# Reaccion-Minimo.net
KiCad netlist of a schematic drawn in EAGLE
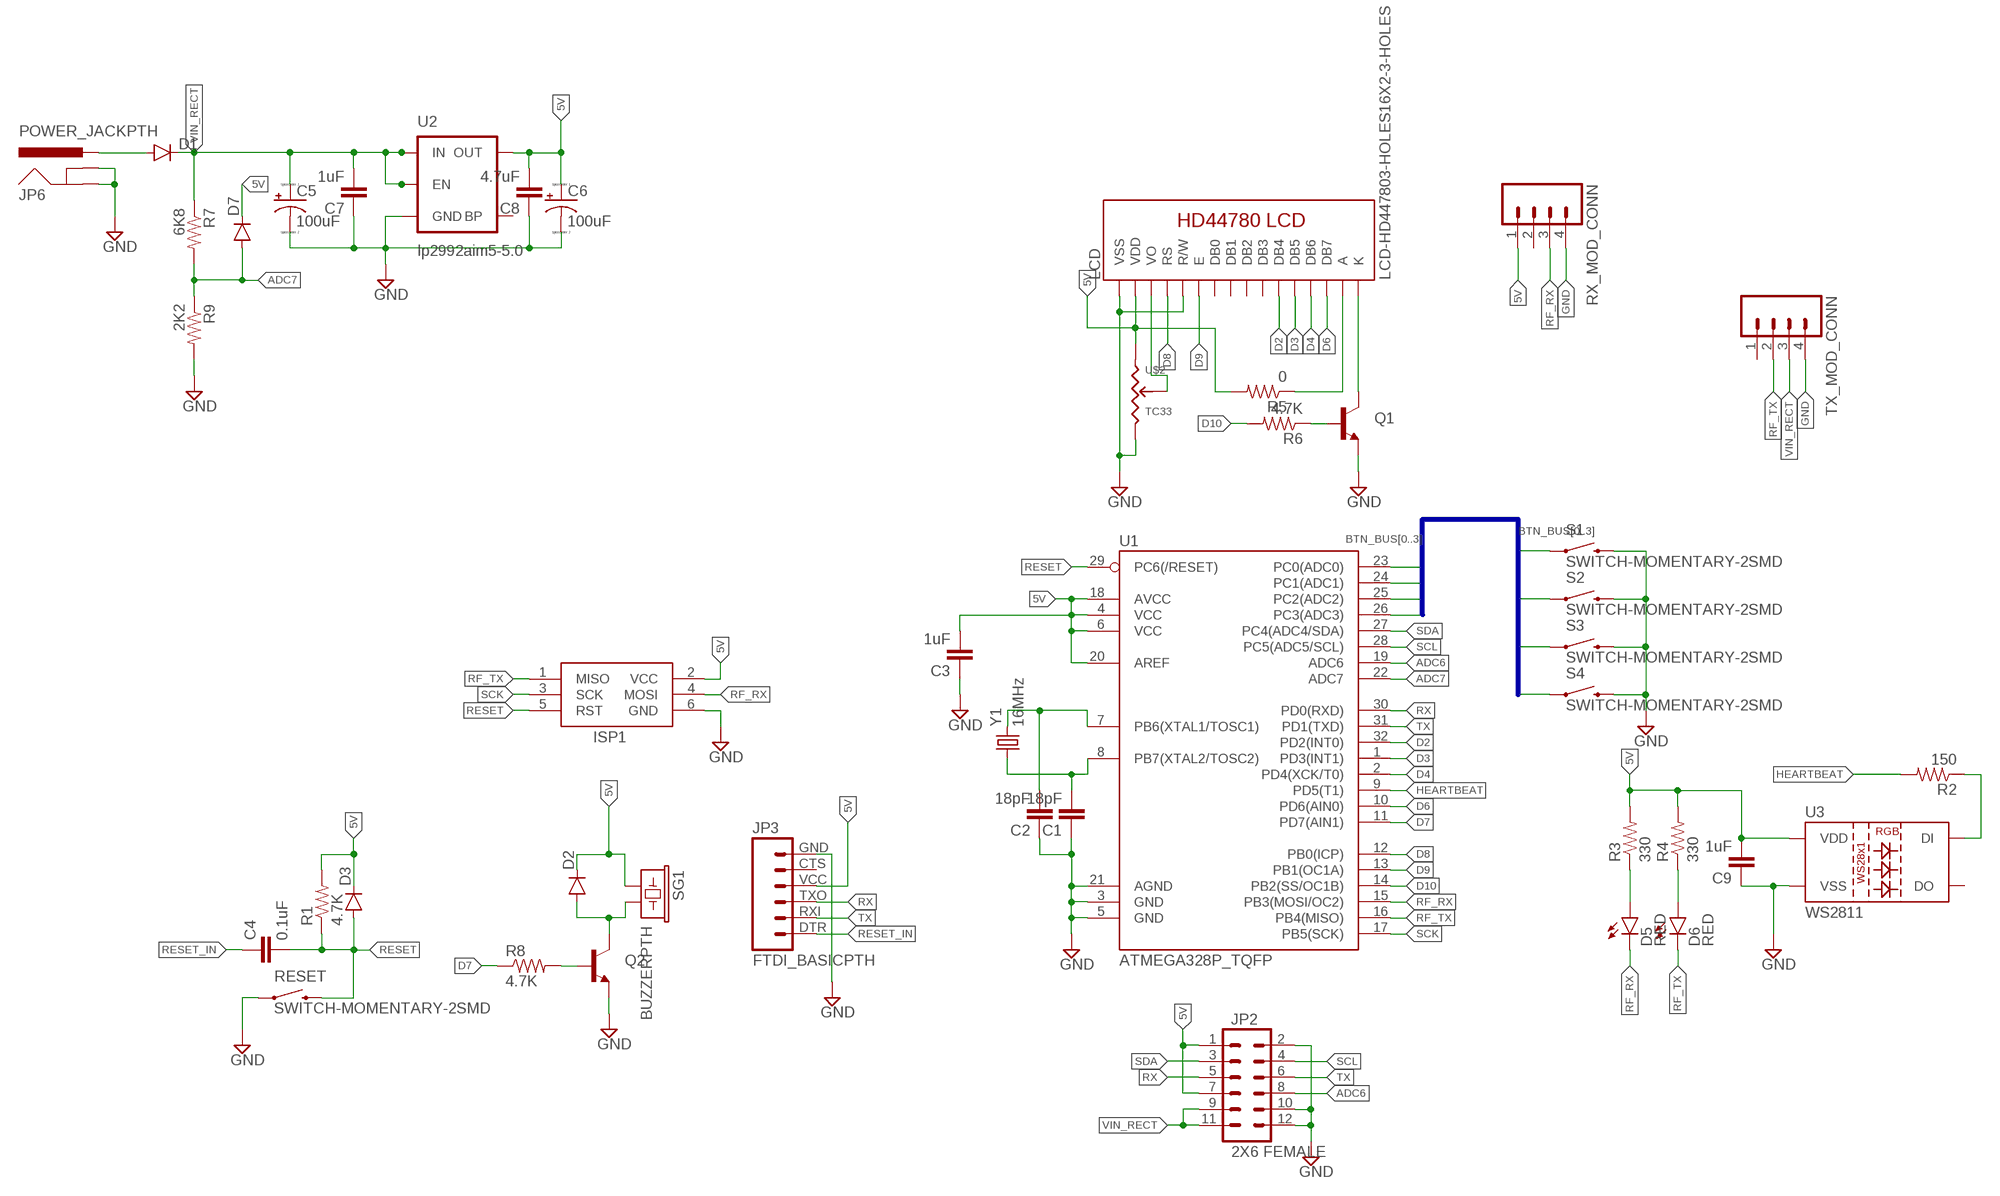
[diagram p0: schematic, sheet 1]

(export (version "E")
  (design (tool "Eeschema 10.0.6"))
  (components
    (comp (ref "C1")
      (value "18pF")
      (footprint "eagle-import:0805")
      (libsource (lib "eagle-import") (part "CAP0805"))
    )
    (comp (ref "C2")
      (value "18pF")
      (footprint "eagle-import:0805")
      (libsource (lib "eagle-import") (part "CAP0805"))
    )
    (comp (ref "C3")
      (value "1uF")
      (footprint "eagle-import:0805")
      (libsource (lib "eagle-import") (part "CAP0805"))
    )
    (comp (ref "C4")
      (value "0.1uF")
      (footprint "eagle-import:0805")
      (libsource (lib "eagle-import") (part "CAP0805"))
    )
    (comp (ref "C5")
      (value "100uF")
      (footprint "eagle-import:C_6032-28R")
      (libsource (lib "eagle-import") (part "CPOL-USC/6032-28R"))
    )
    (comp (ref "C6")
      (value "100uF")
      (footprint "eagle-import:T_3528-12R")
      (libsource (lib "eagle-import") (part "CPOL-USB/3528-21R"))
    )
    (comp (ref "C7")
      (value "1uF")
      (footprint "eagle-import:0805")
      (libsource (lib "eagle-import") (part "CAP0805"))
    )
    (comp (ref "C8")
      (value "4.7uF")
      (footprint "eagle-import:0805")
      (libsource (lib "eagle-import") (part "CAP0805"))
    )
    (comp (ref "C9")
      (value "1uF")
      (footprint "eagle-import:0805")
      (libsource (lib "eagle-import") (part "CAP0805"))
    )
    (comp (ref "D1")
      (value "DIODESMB")
      (footprint "eagle-import:SMB-DIODE")
      (libsource (lib "eagle-import") (part "DIODESMB"))
    )
    (comp (ref "D2")
      (value "DIODESOD123")
      (footprint "eagle-import:SOD-123")
      (libsource (lib "eagle-import") (part "DIODESOD123"))
    )
    (comp (ref "D3")
      (value "DIODESOD123")
      (footprint "eagle-import:SOD-123")
      (libsource (lib "eagle-import") (part "DIODESOD123"))
    )
    (comp (ref "D5")
      (value "RED")
      (footprint "eagle-import:LED-1206")
      (libsource (lib "eagle-import") (part "LED-RED1206"))
    )
    (comp (ref "D6")
      (value "RED")
      (footprint "eagle-import:LED-1206")
      (libsource (lib "eagle-import") (part "LED-RED1206"))
    )
    (comp (ref "D7")
      (value "DIODESOD123")
      (footprint "eagle-import:SOD-123")
      (libsource (lib "eagle-import") (part "DIODESOD123"))
    )
    (comp (ref "ISP1")
      (value "AVRISP-6")
      (footprint "eagle-import:AVRISP")
      (libsource (lib "eagle-import") (part "AVRISP-6"))
    )
    (comp (ref "JP2")
      (value "2X6 FEMALE")
      (footprint "eagle-import:2X6")
      (libsource (lib "eagle-import") (part "M06X2PTH_FEMALE"))
    )
    (comp (ref "JP3")
      (value "FTDI_BASICPTH")
      (footprint "eagle-import:FTDI_BASIC")
      (libsource (lib "eagle-import") (part "FTDI_BASICPTH"))
    )
    (comp (ref "JP6")
      (value "POWER_JACKPTH")
      (footprint "eagle-import:POWER_JACK_PTH")
      (libsource (lib "eagle-import") (part "POWER_JACKPTH"))
    )
    (comp (ref "LCD")
      (value "LCD-HD447803-HOLES16X2-3-HOLES")
      (footprint "eagle-import:LCD-16X2-3HOLES")
      (libsource (lib "eagle-import") (part "LCD-HD4478016X2-3-HOLES3-HOLES"))
    )
    (comp (ref "Q1")
      (value "TRANSISTOR_NPNSOT23-3")
      (footprint "eagle-import:SOT23-3")
      (libsource (lib "eagle-import") (part "TRANSISTOR_NPNSOT23-3"))
    )
    (comp (ref "Q2")
      (value "TRANSISTOR_NPNSOT23-3")
      (footprint "eagle-import:SOT23-3")
      (libsource (lib "eagle-import") (part "TRANSISTOR_NPNSOT23-3"))
    )
    (comp (ref "R1")
      (value "4.7K")
      (footprint "eagle-import:0805")
      (libsource (lib "eagle-import") (part "RESISTOR0805-RES"))
    )
    (comp (ref "R2")
      (value "150")
      (footprint "eagle-import:0805")
      (libsource (lib "eagle-import") (part "RESISTOR0805-RES"))
    )
    (comp (ref "R3")
      (value "330")
      (footprint "eagle-import:0805")
      (libsource (lib "eagle-import") (part "RESISTOR0805-RES"))
    )
    (comp (ref "R4")
      (value "330")
      (footprint "eagle-import:0805")
      (libsource (lib "eagle-import") (part "RESISTOR0805-RES"))
    )
    (comp (ref "R5")
      (value "0")
      (footprint "eagle-import:0805")
      (libsource (lib "eagle-import") (part "RESISTOR0805-RES"))
    )
    (comp (ref "R6")
      (value "4.7K")
      (footprint "eagle-import:0805")
      (libsource (lib "eagle-import") (part "RESISTOR0805-RES"))
    )
    (comp (ref "R7")
      (value "6K8")
      (footprint "eagle-import:0805")
      (libsource (lib "eagle-import") (part "RESISTOR0805-RES"))
    )
    (comp (ref "R8")
      (value "4.7K")
      (footprint "eagle-import:0805")
      (libsource (lib "eagle-import") (part "RESISTOR0805-RES"))
    )
    (comp (ref "R9")
      (value "2K2")
      (footprint "eagle-import:0805")
      (libsource (lib "eagle-import") (part "RESISTOR0805-RES"))
    )
    (comp (ref "RESET")
      (value "SWITCH-MOMENTARY-2SMD")
      (footprint "eagle-import:TACTILE-SWITCH-SMD")
      (libsource (lib "eagle-import") (part "SWITCH-MOMENTARY-2SMD"))
    )
    (comp (ref "RX_MOD_CONN")
      (value "M04PTH")
      (footprint "eagle-import:1X04")
      (libsource (lib "eagle-import") (part "M04PTH"))
    )
    (comp (ref "S1")
      (value "SWITCH-MOMENTARY-2SMD")
      (footprint "eagle-import:TACTILE-SWITCH-SMD")
      (libsource (lib "eagle-import") (part "SWITCH-MOMENTARY-2SMD"))
    )
    (comp (ref "S2")
      (value "SWITCH-MOMENTARY-2SMD")
      (footprint "eagle-import:TACTILE-SWITCH-SMD")
      (libsource (lib "eagle-import") (part "SWITCH-MOMENTARY-2SMD"))
    )
    (comp (ref "S3")
      (value "SWITCH-MOMENTARY-2SMD")
      (footprint "eagle-import:TACTILE-SWITCH-SMD")
      (libsource (lib "eagle-import") (part "SWITCH-MOMENTARY-2SMD"))
    )
    (comp (ref "S4")
      (value "SWITCH-MOMENTARY-2SMD")
      (footprint "eagle-import:TACTILE-SWITCH-SMD")
      (libsource (lib "eagle-import") (part "SWITCH-MOMENTARY-2SMD"))
    )
    (comp (ref "SG1")
      (value "BUZZERPTH")
      (footprint "eagle-import:BUZZER-12MM")
      (libsource (lib "eagle-import") (part "BUZZERPTH"))
    )
    (comp (ref "TX_MOD_CONN")
      (value "M04PTH")
      (footprint "eagle-import:1X04")
      (libsource (lib "eagle-import") (part "M04PTH"))
    )
    (comp (ref "U$2")
      (value "TC33")
      (footprint "eagle-import:TC33")
      (libsource (lib "eagle-import") (part "TC33"))
    )
    (comp (ref "U1")
      (value "ATMEGA328P_TQFP")
      (footprint "eagle-import:TQFP32-08")
      (libsource (lib "eagle-import") (part "ATMEGA328P_TQFP"))
    )
    (comp (ref "U2")
      (value "lp2992aim5-5.0")
      (footprint "eagle-import:SOT23-5")
      (libsource (lib "eagle-import") (part "V_REG_MIC52195V"))
    )
    (comp (ref "U3")
      (value "WS2811")
      (footprint "eagle-import:LED-TRICOLOR-5050-IC")
      (libsource (lib "eagle-import") (part "LED-TRICOLOR-5050-ICWS2811"))
    )
    (comp (ref "Y1")
      (value "16MHz")
      (footprint "eagle-import:CRYSTAL-SMD-5X3")
      (libsource (lib "eagle-import") (part "CRYSTAL5X3"))
    )
  )
  (nets
    (net (code "1") (name "/BTN_BUS0") (class "Default")
      (node (ref "S1") (pin "1") (pinfunction "1_1") (pintype "passive"))
      (node (ref "U1") (pin "23") (pinfunction "PC0(ADC0)_23") (pintype "bidirectional"))
    )
    (net (code "2") (name "/BTN_BUS1") (class "Default")
      (node (ref "S2") (pin "1") (pinfunction "1_1") (pintype "passive"))
      (node (ref "U1") (pin "24") (pinfunction "PC1(ADC1)_24") (pintype "bidirectional"))
    )
    (net (code "3") (name "/BTN_BUS2") (class "Default")
      (node (ref "S3") (pin "1") (pinfunction "1_1") (pintype "passive"))
      (node (ref "U1") (pin "25") (pinfunction "PC2(ADC2)_25") (pintype "bidirectional"))
    )
    (net (code "4") (name "/BTN_BUS3") (class "Default")
      (node (ref "S4") (pin "1") (pinfunction "1_1") (pintype "passive"))
      (node (ref "U1") (pin "26") (pinfunction "PC3(ADC3)_26") (pintype "bidirectional"))
    )
    (net (code "6") (name "5V") (class "Default")
      (node (ref "C3") (pin "2") (pinfunction "2_2") (pintype "passive"))
      (node (ref "C6") (pin "+") (pinfunction "+_+") (pintype "passive"))
      (node (ref "C8") (pin "2") (pinfunction "2_2") (pintype "passive"))
      (node (ref "C9") (pin "2") (pinfunction "2_2") (pintype "passive"))
      (node (ref "D2") (pin "C") (pinfunction "C_C") (pintype "passive"))
      (node (ref "D3") (pin "C") (pinfunction "C_C") (pintype "passive"))
      (node (ref "D7") (pin "C") (pinfunction "C_C") (pintype "passive"))
      (node (ref "ISP1") (pin "2") (pinfunction "VCC_2") (pintype "power_in"))
      (node (ref "JP2") (pin "1") (pinfunction "1_1") (pintype "passive"))
      (node (ref "JP2") (pin "7") (pinfunction "7_7") (pintype "passive"))
      (node (ref "JP3") (pin "VCC") (pinfunction "4_VCC") (pintype "passive"))
      (node (ref "LCD") (pin "2") (pinfunction "VDD_2") (pintype "power_in"))
      (node (ref "R1") (pin "2") (pinfunction "2_2") (pintype "passive"))
      (node (ref "R3") (pin "2") (pinfunction "2_2") (pintype "passive"))
      (node (ref "R4") (pin "2") (pinfunction "2_2") (pintype "passive"))
      (node (ref "R5") (pin "2") (pinfunction "2_2") (pintype "passive"))
      (node (ref "RX_MOD_CONN") (pin "1") (pinfunction "1_1") (pintype "passive"))
      (node (ref "SG1") (pin "+") (pinfunction "1_+") (pintype "passive"))
      (node (ref "U$2") (pin "1") (pinfunction "1_1") (pintype "bidirectional"))
      (node (ref "U1") (pin "18") (pinfunction "AVCC_18") (pintype "bidirectional"))
      (node (ref "U1") (pin "20") (pinfunction "AREF_20") (pintype "bidirectional"))
      (node (ref "U1") (pin "4") (pinfunction "VCC_4") (pintype "bidirectional"))
      (node (ref "U1") (pin "6") (pinfunction "VCC_6") (pintype "bidirectional"))
      (node (ref "U2") (pin "5") (pinfunction "OUT_5") (pintype "passive"))
      (node (ref "U3") (pin "3") (pinfunction "VDD_3") (pintype "bidirectional"))
      (node (ref "U3") (pin "5") (pinfunction "VDD_5") (pintype "bidirectional"))
    )
    (net (code "7") (name "ADC6") (class "Default")
      (node (ref "JP2") (pin "8") (pinfunction "8_8") (pintype "passive"))
      (node (ref "U1") (pin "19") (pinfunction "ADC6_19") (pintype "bidirectional"))
    )
    (net (code "8") (name "ADC7") (class "Default")
      (node (ref "D7") (pin "A") (pinfunction "A_A") (pintype "passive"))
      (node (ref "R7") (pin "2") (pinfunction "2_2") (pintype "passive"))
      (node (ref "R9") (pin "1") (pinfunction "1_1") (pintype "passive"))
      (node (ref "U1") (pin "22") (pinfunction "ADC7_22") (pintype "bidirectional"))
    )
    (net (code "9") (name "D2") (class "Default")
      (node (ref "LCD") (pin "11") (pinfunction "DB4_11") (pintype "bidirectional"))
      (node (ref "U1") (pin "32") (pinfunction "PD2(INT0)_32") (pintype "bidirectional"))
    )
    (net (code "10") (name "D3") (class "Default")
      (node (ref "LCD") (pin "12") (pinfunction "DB5_12") (pintype "bidirectional"))
      (node (ref "U1") (pin "1") (pinfunction "PD3(INT1)_1") (pintype "bidirectional"))
    )
    (net (code "11") (name "D4") (class "Default")
      (node (ref "LCD") (pin "13") (pinfunction "DB6_13") (pintype "bidirectional"))
      (node (ref "U1") (pin "2") (pinfunction "PD4(XCK/T0)_2") (pintype "bidirectional"))
    )
    (net (code "12") (name "D6") (class "Default")
      (node (ref "LCD") (pin "14") (pinfunction "DB7_14") (pintype "bidirectional"))
      (node (ref "U1") (pin "10") (pinfunction "PD6(AIN0)_10") (pintype "bidirectional"))
    )
    (net (code "13") (name "D7") (class "Default")
      (node (ref "R8") (pin "1") (pinfunction "1_1") (pintype "passive"))
      (node (ref "U1") (pin "11") (pinfunction "PD7(AIN1)_11") (pintype "bidirectional"))
    )
    (net (code "14") (name "D8") (class "Default")
      (node (ref "LCD") (pin "4") (pinfunction "RS_4") (pintype "input"))
      (node (ref "U1") (pin "12") (pinfunction "PB0(ICP)_12") (pintype "bidirectional"))
    )
    (net (code "15") (name "D9") (class "Default")
      (node (ref "LCD") (pin "6") (pinfunction "E_6") (pintype "input"))
      (node (ref "U1") (pin "13") (pinfunction "PB1(OC1A)_13") (pintype "bidirectional"))
    )
    (net (code "16") (name "D10") (class "Default")
      (node (ref "R6") (pin "2") (pinfunction "2_2") (pintype "passive"))
      (node (ref "U1") (pin "14") (pinfunction "PB2(SS/OC1B)_14") (pintype "bidirectional"))
    )
    (net (code "17") (name "GND") (class "Default")
      (node (ref "C1") (pin "1") (pinfunction "1_1") (pintype "passive"))
      (node (ref "C2") (pin "1") (pinfunction "1_1") (pintype "passive"))
      (node (ref "C3") (pin "1") (pinfunction "1_1") (pintype "passive"))
      (node (ref "C5") (pin "-") (pinfunction "-_-") (pintype "passive"))
      (node (ref "C6") (pin "-") (pinfunction "-_-") (pintype "passive"))
      (node (ref "C7") (pin "1") (pinfunction "1_1") (pintype "passive"))
      (node (ref "C8") (pin "1") (pinfunction "1_1") (pintype "passive"))
      (node (ref "C9") (pin "1") (pinfunction "1_1") (pintype "passive"))
      (node (ref "ISP1") (pin "6") (pinfunction "GND_6") (pintype "power_in"))
      (node (ref "JP2") (pin "10") (pinfunction "10_10") (pintype "passive"))
      (node (ref "JP2") (pin "12") (pinfunction "12_12") (pintype "passive"))
      (node (ref "JP2") (pin "2") (pinfunction "2_2") (pintype "passive"))
      (node (ref "JP3") (pin "GND") (pinfunction "6_GND") (pintype "passive"))
      (node (ref "JP6") (pin "GND") (pinfunction "GND_GND") (pintype "bidirectional"))
      (node (ref "JP6") (pin "GNDBREAK") (pinfunction "GNDBREAK_GNDBREAK") (pintype "bidirectional"))
      (node (ref "LCD") (pin "1") (pinfunction "VSS_1") (pintype "power_in"))
      (node (ref "LCD") (pin "5") (pinfunction "R/W_5") (pintype "input"))
      (node (ref "Q1") (pin "2") (pinfunction "E_2") (pintype "passive"))
      (node (ref "Q2") (pin "2") (pinfunction "E_2") (pintype "passive"))
      (node (ref "R9") (pin "2") (pinfunction "2_2") (pintype "passive"))
      (node (ref "RESET") (pin "1") (pinfunction "1_1") (pintype "passive"))
      (node (ref "RX_MOD_CONN") (pin "4") (pinfunction "4_4") (pintype "passive"))
      (node (ref "S1") (pin "3") (pinfunction "2_3") (pintype "passive"))
      (node (ref "S2") (pin "3") (pinfunction "2_3") (pintype "passive"))
      (node (ref "S3") (pin "3") (pinfunction "2_3") (pintype "passive"))
      (node (ref "S4") (pin "3") (pinfunction "2_3") (pintype "passive"))
      (node (ref "TX_MOD_CONN") (pin "4") (pinfunction "4_4") (pintype "passive"))
      (node (ref "U$2") (pin "3") (pinfunction "3_3") (pintype "bidirectional"))
      (node (ref "U1") (pin "21") (pinfunction "AGND_21") (pintype "bidirectional"))
      (node (ref "U1") (pin "3") (pinfunction "GND_3") (pintype "bidirectional"))
      (node (ref "U1") (pin "5") (pinfunction "GND_5") (pintype "bidirectional"))
      (node (ref "U2") (pin "2") (pinfunction "GND_2") (pintype "input"))
      (node (ref "U3") (pin "6") (pinfunction "VSS_6") (pintype "bidirectional"))
    )
    (net (code "18") (name "HEARTBEAT") (class "Default")
      (node (ref "R2") (pin "2") (pinfunction "2_2") (pintype "passive"))
      (node (ref "U1") (pin "9") (pinfunction "PD5(T1)_9") (pintype "bidirectional"))
    )
    (net (code "19") (name "Net-(D1-PadA)") (class "Default")
      (node (ref "D1") (pin "A") (pinfunction "A_A") (pintype "passive"))
      (node (ref "JP6") (pin "PWR") (pinfunction "PWR_PWR") (pintype "bidirectional"))
    )
    (net (code "20") (name "Net-(D5-PadA)") (class "Default")
      (node (ref "D5") (pin "A") (pinfunction "A_A") (pintype "passive"))
      (node (ref "R3") (pin "1") (pinfunction "1_1") (pintype "passive"))
    )
    (net (code "21") (name "Net-(D6-PadA)") (class "Default")
      (node (ref "D6") (pin "A") (pinfunction "A_A") (pintype "passive"))
      (node (ref "R4") (pin "1") (pinfunction "1_1") (pintype "passive"))
    )
    (net (code "22") (name "Net-(LCD-A)") (class "Default")
      (node (ref "LCD") (pin "15") (pinfunction "A_15") (pintype "power_in"))
      (node (ref "R5") (pin "1") (pinfunction "1_1") (pintype "passive"))
    )
    (net (code "23") (name "Net-(LCD-K)") (class "Default")
      (node (ref "LCD") (pin "16") (pinfunction "K_16") (pintype "power_in"))
      (node (ref "Q1") (pin "3") (pinfunction "C_3") (pintype "passive"))
    )
    (net (code "24") (name "Net-(LCD-VO)") (class "Default")
      (node (ref "LCD") (pin "3") (pinfunction "VO_3") (pintype "bidirectional"))
      (node (ref "U$2") (pin "2") (pinfunction "2_2") (pintype "bidirectional"))
    )
    (net (code "25") (name "Net-(Q1-B)") (class "Default")
      (node (ref "Q1") (pin "1") (pinfunction "B_1") (pintype "passive"))
      (node (ref "R6") (pin "1") (pinfunction "1_1") (pintype "passive"))
    )
    (net (code "26") (name "Net-(Q2-B)") (class "Default")
      (node (ref "Q2") (pin "1") (pinfunction "B_1") (pintype "passive"))
      (node (ref "R8") (pin "2") (pinfunction "2_2") (pintype "passive"))
    )
    (net (code "27") (name "Net-(Q2-C)") (class "Default")
      (node (ref "D2") (pin "A") (pinfunction "A_A") (pintype "passive"))
      (node (ref "Q2") (pin "3") (pinfunction "C_3") (pintype "passive"))
      (node (ref "SG1") (pin "-") (pinfunction "2_-") (pintype "passive"))
    )
    (net (code "28") (name "Net-(U1-PB6(XTAL1{slash}TOSC1))") (class "Default")
      (node (ref "C2") (pin "2") (pinfunction "2_2") (pintype "passive"))
      (node (ref "U1") (pin "7") (pinfunction "PB6(XTAL1/TOSC1)_7") (pintype "bidirectional"))
      (node (ref "Y1") (pin "3") (pinfunction "2_3") (pintype "passive"))
    )
    (net (code "29") (name "Net-(U1-PB7(XTAL2{slash}TOSC2))") (class "Default")
      (node (ref "C1") (pin "2") (pinfunction "2_2") (pintype "passive"))
      (node (ref "U1") (pin "8") (pinfunction "PB7(XTAL2/TOSC2)_8") (pintype "bidirectional"))
      (node (ref "Y1") (pin "1") (pinfunction "1_1") (pintype "passive"))
    )
    (net (code "30") (name "Net-(U3-DI)") (class "Default")
      (node (ref "R2") (pin "1") (pinfunction "1_1") (pintype "passive"))
      (node (ref "U3") (pin "2") (pinfunction "DI_2") (pintype "bidirectional"))
    )
    (net (code "31") (name "RESET") (class "Default")
      (node (ref "C4") (pin "2") (pinfunction "2_2") (pintype "passive"))
      (node (ref "D3") (pin "A") (pinfunction "A_A") (pintype "passive"))
      (node (ref "ISP1") (pin "5") (pinfunction "RST_5") (pintype "output"))
      (node (ref "R1") (pin "1") (pinfunction "1_1") (pintype "passive"))
      (node (ref "RESET") (pin "3") (pinfunction "2_3") (pintype "passive"))
      (node (ref "U1") (pin "29") (pinfunction "PC6(/RESET)_29") (pintype "bidirectional"))
    )
    (net (code "32") (name "RESET_IN") (class "Default")
      (node (ref "C4") (pin "1") (pinfunction "1_1") (pintype "passive"))
      (node (ref "JP3") (pin "DTR") (pinfunction "1_DTR") (pintype "passive"))
    )
    (net (code "33") (name "RF_RX") (class "Default")
      (node (ref "D5") (pin "C") (pinfunction "C_C") (pintype "passive"))
      (node (ref "ISP1") (pin "4") (pinfunction "MOSI_4") (pintype "output"))
      (node (ref "RX_MOD_CONN") (pin "3") (pinfunction "3_3") (pintype "passive"))
      (node (ref "U1") (pin "15") (pinfunction "PB3(MOSI/OC2)_15") (pintype "bidirectional"))
    )
    (net (code "34") (name "RF_TX") (class "Default")
      (node (ref "D6") (pin "C") (pinfunction "C_C") (pintype "passive"))
      (node (ref "ISP1") (pin "1") (pinfunction "MISO_1") (pintype "input"))
      (node (ref "TX_MOD_CONN") (pin "2") (pinfunction "2_2") (pintype "passive"))
      (node (ref "U1") (pin "16") (pinfunction "PB4(MISO)_16") (pintype "bidirectional"))
    )
    (net (code "35") (name "RX") (class "Default")
      (node (ref "JP2") (pin "5") (pinfunction "5_5") (pintype "passive"))
      (node (ref "JP3") (pin "TXO") (pinfunction "3_TXO") (pintype "passive"))
      (node (ref "U1") (pin "30") (pinfunction "PD0(RXD)_30") (pintype "bidirectional"))
    )
    (net (code "36") (name "SCK") (class "Default")
      (node (ref "ISP1") (pin "3") (pinfunction "SCK_3") (pintype "output"))
      (node (ref "U1") (pin "17") (pinfunction "PB5(SCK)_17") (pintype "bidirectional"))
    )
    (net (code "37") (name "SCL") (class "Default")
      (node (ref "JP2") (pin "4") (pinfunction "4_4") (pintype "passive"))
      (node (ref "U1") (pin "28") (pinfunction "PC5(ADC5/SCL)_28") (pintype "bidirectional"))
    )
    (net (code "38") (name "SDA") (class "Default")
      (node (ref "JP2") (pin "3") (pinfunction "3_3") (pintype "passive"))
      (node (ref "U1") (pin "27") (pinfunction "PC4(ADC4/SDA)_27") (pintype "bidirectional"))
    )
    (net (code "39") (name "TX") (class "Default")
      (node (ref "JP2") (pin "6") (pinfunction "6_6") (pintype "passive"))
      (node (ref "JP3") (pin "RXI") (pinfunction "2_RXI") (pintype "passive"))
      (node (ref "U1") (pin "31") (pinfunction "PD1(TXD)_31") (pintype "bidirectional"))
    )
    (net (code "40") (name "VIN_RECT") (class "Default")
      (node (ref "C5") (pin "+") (pinfunction "+_+") (pintype "passive"))
      (node (ref "C7") (pin "2") (pinfunction "2_2") (pintype "passive"))
      (node (ref "D1") (pin "C") (pinfunction "C_C") (pintype "passive"))
      (node (ref "JP2") (pin "11") (pinfunction "11_11") (pintype "passive"))
      (node (ref "JP2") (pin "9") (pinfunction "9_9") (pintype "passive"))
      (node (ref "R7") (pin "1") (pinfunction "1_1") (pintype "passive"))
      (node (ref "TX_MOD_CONN") (pin "3") (pinfunction "3_3") (pintype "passive"))
      (node (ref "U2") (pin "1") (pinfunction "IN_1") (pintype "input"))
      (node (ref "U2") (pin "3") (pinfunction "EN_3") (pintype "input"))
    )
    (net (code "41") (name "unconnected-(JP3-5-PadCTS)") (class "Default")
      (node (ref "JP3") (pin "CTS") (pinfunction "5_CTS") (pintype "passive"))
    )
    (net (code "42") (name "unconnected-(LCD-DB0-Pad7)") (class "Default")
      (node (ref "LCD") (pin "7") (pinfunction "DB0_7") (pintype "bidirectional"))
    )
    (net (code "43") (name "unconnected-(LCD-DB1-Pad8)") (class "Default")
      (node (ref "LCD") (pin "8") (pinfunction "DB1_8") (pintype "bidirectional"))
    )
    (net (code "44") (name "unconnected-(LCD-DB2-Pad9)") (class "Default")
      (node (ref "LCD") (pin "9") (pinfunction "DB2_9") (pintype "bidirectional"))
    )
    (net (code "45") (name "unconnected-(LCD-DB3-Pad10)") (class "Default")
      (node (ref "LCD") (pin "10") (pinfunction "DB3_10") (pintype "bidirectional"))
    )
    (net (code "46") (name "unconnected-(RX_MOD_CONN-Pad2)") (class "Default")
      (node (ref "RX_MOD_CONN") (pin "2") (pinfunction "2_2") (pintype "passive"))
    )
    (net (code "47") (name "unconnected-(TX_MOD_CONN-Pad1)") (class "Default")
      (node (ref "TX_MOD_CONN") (pin "1") (pinfunction "1_1") (pintype "passive"))
    )
    (net (code "48") (name "unconnected-(U2-BP-Pad4)") (class "Default")
      (node (ref "U2") (pin "4") (pinfunction "BP_4") (pintype "input"))
    )
    (net (code "49") (name "unconnected-(U3-DO-Pad1)") (class "Default")
      (node (ref "U3") (pin "1") (pinfunction "DO_1") (pintype "bidirectional"))
    )
  )
)
